# easyeda_source_code.net
KiCad netlist of a schematic drawn in EasyEDA
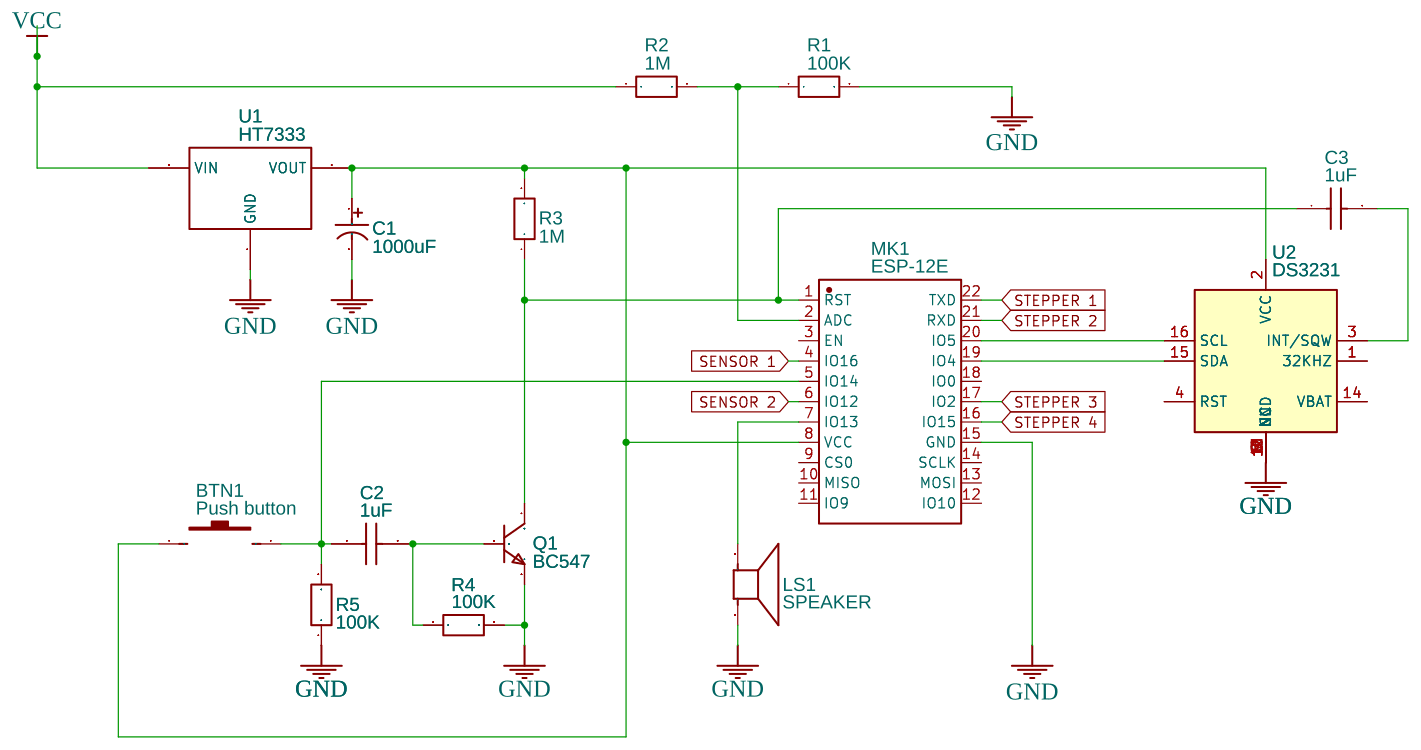
[diagram p0: schematic sheet]

(export (version "E")
  (design (tool "Eeschema 10.0.6"))
  (components
    (comp (ref "BTN1")
      (value "Push button")
      (fields
        (field (name "BOM_Manufacturer Part") "Switch3x4x2")
        (field (name "BOM_Supplier Part") "C26638")
      )
      (libsource (lib "") (part "Switch3x4x2"))
    )
    (comp (ref "C1")
      (value "1000uF")
      (fields
        (field (name "BOM_Manufacturer Part") "1000uF 10V绿金 10*15")
        (field (name "BOM_Supplier Part") "C43339")
      )
      (libsource (lib "") (part "1000uF 10V 10*15"))
    )
    (comp (ref "C2") (value "1uF") (libsource (lib "") (part "CAPACITOR_RevE_Date15jun2010")))
    (comp (ref "C3") (value "1uF") (libsource (lib "") (part "CAPACITOR_RevE_Date15jun2010")))
    (comp (ref "LS1") (value "SPEAKER") (libsource (lib "") (part "SPEAKERPS12")))
    (comp (ref "MK1")
      (value "ESP-12E")
      (fields (field (name "BOM_Supplier Part") "C89297"))
      (libsource (lib "") (part "ESP-12E"))
    )
    (comp (ref "Q1")
      (value "BC547")
      (fields (field (name "BOM_Manufacturer Part") "BC547BTA") (field (name "BOM_Supplier Part") "C258144"))
      (libsource (lib "") (part "BC547BTA"))
    )
    (comp (ref "R1") (value "100K") (libsource (lib "") (part "R_0201_EU_1")))
    (comp (ref "R2") (value "1M") (libsource (lib "") (part "R_0201_EU_1")))
    (comp (ref "R3") (value "1M") (libsource (lib "") (part "R_0201_EU")))
    (comp (ref "R4") (value "100K") (libsource (lib "") (part "R_0201_EU_1")))
    (comp (ref "R5") (value "100K") (libsource (lib "") (part "R_0201_EU")))
    (comp (ref "U1")
      (value "HT7333")
      (fields (field (name "BOM_Manufacturer Part") "HT7333-A") (field (name "BOM_Supplier Part") "C73726"))
      (libsource (lib "") (part "HT7333-A_C73726"))
    )
    (comp (ref "U2") (value "DS3231") (libsource (lib "") (part "DS3231")))
  )
  (nets
    (net (code "1") (name "GND") (class "Default")
      (node (ref "C1") (pin "2") (pinfunction "2_2") (pintype "input"))
      (node (ref "LS1") (pin "P$2") (pinfunction "-_P$2") (pintype "unspecified"))
      (node (ref "MK1") (pin "15") (pinfunction "GND_15") (pintype "unspecified"))
      (node (ref "Q1") (pin "3") (pinfunction "E_3") (pintype "unspecified"))
      (node (ref "R1") (pin "2") (pinfunction "2_2") (pintype "unspecified"))
      (node (ref "R4") (pin "2") (pinfunction "2_2") (pintype "unspecified"))
      (node (ref "R5") (pin "1") (pinfunction "1_1") (pintype "unspecified"))
      (node (ref "U1") (pin "1") (pinfunction "GND_1") (pintype "unspecified"))
      (node (ref "U2") (pin "10") (pinfunction "NC_10") (pintype "unspecified"))
      (node (ref "U2") (pin "11") (pinfunction "NC_11") (pintype "unspecified"))
      (node (ref "U2") (pin "12") (pinfunction "NC_12") (pintype "unspecified"))
      (node (ref "U2") (pin "13") (pinfunction "GND_13") (pintype "bidirectional"))
      (node (ref "U2") (pin "5") (pinfunction "NC_5") (pintype "unspecified"))
      (node (ref "U2") (pin "6") (pinfunction "NC_6") (pintype "unspecified"))
      (node (ref "U2") (pin "7") (pinfunction "NC_7") (pintype "unspecified"))
      (node (ref "U2") (pin "8") (pinfunction "NC_8") (pintype "unspecified"))
      (node (ref "U2") (pin "9") (pinfunction "NC_9") (pintype "unspecified"))
    )
    (net (code "2") (name "Net-(LS1-+)") (class "Default")
      (node (ref "LS1") (pin "P$1") (pinfunction "+_P$1") (pintype "unspecified"))
      (node (ref "MK1") (pin "7") (pinfunction "IO13_7") (pintype "unspecified"))
    )
    (net (code "3") (name "Net-(MK1-ADC)") (class "Default")
      (node (ref "MK1") (pin "2") (pinfunction "ADC_2") (pintype "unspecified"))
      (node (ref "R1") (pin "1") (pinfunction "1_1") (pintype "unspecified"))
      (node (ref "R2") (pin "2") (pinfunction "2_2") (pintype "unspecified"))
    )
    (net (code "4") (name "Net-(MK1-IO4)") (class "Default")
      (node (ref "MK1") (pin "19") (pinfunction "IO4_19") (pintype "unspecified"))
      (node (ref "U2") (pin "15") (pinfunction "SDA_15") (pintype "bidirectional"))
    )
    (net (code "5") (name "Net-(MK1-IO5)") (class "Default")
      (node (ref "MK1") (pin "20") (pinfunction "IO5_20") (pintype "unspecified"))
      (node (ref "U2") (pin "16") (pinfunction "SCL_16") (pintype "input"))
    )
    (net (code "6") (name "Net-(MK1-IO14)") (class "Default")
      (node (ref "BTN1") (pin "2") (pinfunction "2_2") (pintype "input"))
      (node (ref "C2") (pin "1") (pintype "unspecified"))
      (node (ref "MK1") (pin "5") (pinfunction "IO14_5") (pintype "unspecified"))
      (node (ref "R5") (pin "2") (pinfunction "2_2") (pintype "unspecified"))
    )
    (net (code "7") (name "Net-(MK1-RST)") (class "Default")
      (node (ref "C3") (pin "1") (pintype "unspecified"))
      (node (ref "MK1") (pin "1") (pinfunction "RST_1") (pintype "unspecified"))
      (node (ref "Q1") (pin "1") (pinfunction "C_1") (pintype "unspecified"))
      (node (ref "R3") (pin "1") (pinfunction "1_1") (pintype "unspecified"))
    )
    (net (code "8") (name "Net-(MK1-VCC)") (class "Default")
      (node (ref "BTN1") (pin "1") (pinfunction "1_1") (pintype "input"))
      (node (ref "C1") (pin "1") (pinfunction "1_1") (pintype "input"))
      (node (ref "MK1") (pin "8") (pinfunction "VCC_8") (pintype "unspecified"))
      (node (ref "R3") (pin "2") (pinfunction "2_2") (pintype "unspecified"))
      (node (ref "U1") (pin "3") (pinfunction "VOUT_3") (pintype "unspecified"))
      (node (ref "U2") (pin "2") (pinfunction "VCC_2") (pintype "bidirectional"))
    )
    (net (code "9") (name "Net-(Q1-B)") (class "Default")
      (node (ref "C2") (pin "2") (pintype "unspecified"))
      (node (ref "Q1") (pin "2") (pinfunction "B_2") (pintype "unspecified"))
      (node (ref "R4") (pin "1") (pinfunction "1_1") (pintype "unspecified"))
    )
    (net (code "10") (name "Net-(U2-INT{slash}SQW)") (class "Default")
      (node (ref "C3") (pin "2") (pintype "unspecified"))
      (node (ref "U2") (pin "3") (pinfunction "INT/SQW_3") (pintype "unspecified"))
    )
    (net (code "11") (name "SENSOR 1") (class "Default")
      (node (ref "MK1") (pin "4") (pinfunction "IO16_4") (pintype "unspecified"))
    )
    (net (code "12") (name "SENSOR 2") (class "Default")
      (node (ref "MK1") (pin "6") (pinfunction "IO12_6") (pintype "unspecified"))
    )
    (net (code "13") (name "STEPPER 1") (class "Default")
      (node (ref "MK1") (pin "22") (pinfunction "TXD_22") (pintype "unspecified"))
    )
    (net (code "14") (name "STEPPER 2") (class "Default")
      (node (ref "MK1") (pin "21") (pinfunction "RXD_21") (pintype "unspecified"))
    )
    (net (code "15") (name "STEPPER 3") (class "Default")
      (node (ref "MK1") (pin "17") (pinfunction "IO2_17") (pintype "unspecified"))
    )
    (net (code "16") (name "STEPPER 4") (class "Default")
      (node (ref "MK1") (pin "16") (pinfunction "IO15_16") (pintype "unspecified"))
    )
    (net (code "17") (name "VCC") (class "Default")
      (node (ref "R2") (pin "1") (pinfunction "1_1") (pintype "unspecified"))
      (node (ref "U1") (pin "2") (pinfunction "VIN_2") (pintype "unspecified"))
    )
    (net (code "18") (name "unconnected-(MK1-CS0-Pad9)") (class "Default")
      (node (ref "MK1") (pin "9") (pinfunction "CS0_9") (pintype "unspecified"))
    )
    (net (code "19") (name "unconnected-(MK1-EN-Pad3)") (class "Default")
      (node (ref "MK1") (pin "3") (pinfunction "EN_3") (pintype "unspecified"))
    )
    (net (code "20") (name "unconnected-(MK1-IO0-Pad18)") (class "Default")
      (node (ref "MK1") (pin "18") (pinfunction "IO0_18") (pintype "unspecified"))
    )
    (net (code "21") (name "unconnected-(MK1-IO9-Pad11)") (class "Default")
      (node (ref "MK1") (pin "11") (pinfunction "IO9_11") (pintype "unspecified"))
    )
    (net (code "22") (name "unconnected-(MK1-IO10-Pad12)") (class "Default")
      (node (ref "MK1") (pin "12") (pinfunction "IO10_12") (pintype "unspecified"))
    )
    (net (code "23") (name "unconnected-(MK1-MISO-Pad10)") (class "Default")
      (node (ref "MK1") (pin "10") (pinfunction "MISO_10") (pintype "unspecified"))
    )
    (net (code "24") (name "unconnected-(MK1-MOSI-Pad13)") (class "Default")
      (node (ref "MK1") (pin "13") (pinfunction "MOSI_13") (pintype "unspecified"))
    )
    (net (code "25") (name "unconnected-(MK1-SCLK-Pad14)") (class "Default")
      (node (ref "MK1") (pin "14") (pinfunction "SCLK_14") (pintype "unspecified"))
    )
    (net (code "26") (name "unconnected-(U2-32KHZ-Pad1)") (class "Default")
      (node (ref "U2") (pin "1") (pinfunction "32KHZ_1") (pintype "unspecified"))
    )
    (net (code "27") (name "unconnected-(U2-RST-Pad4)") (class "Default")
      (node (ref "U2") (pin "4") (pinfunction "RST_4") (pintype "bidirectional"))
    )
    (net (code "28") (name "unconnected-(U2-VBAT-Pad14)") (class "Default")
      (node (ref "U2") (pin "14") (pinfunction "VBAT_14") (pintype "bidirectional"))
    )
  )
)
